# floppyemu.net
KiCad netlist of a schematic drawn in EAGLE
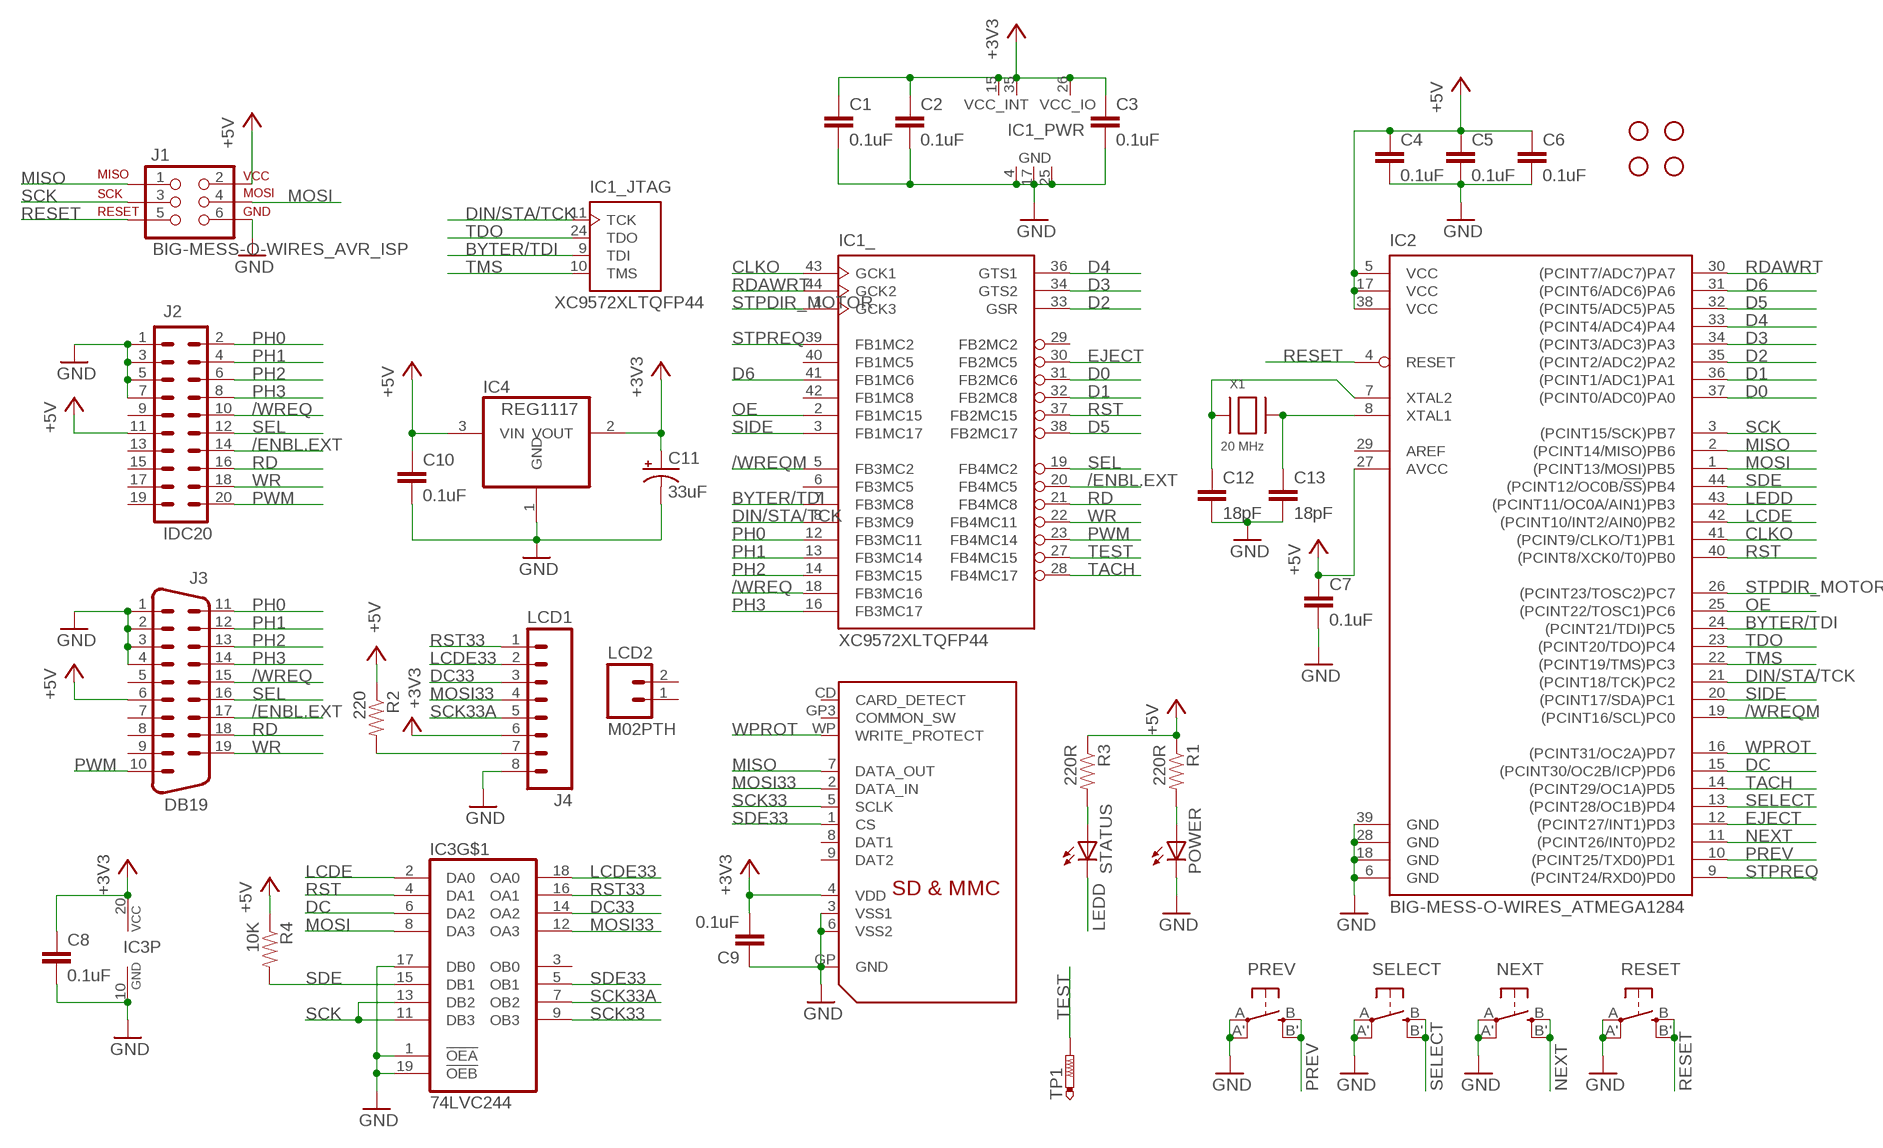
[diagram p0: schematic, sheet 1]

(export (version "E")
  (design (tool "Eeschema 10.0.6"))
  (components
    (comp (ref "C1")
      (value "0.1uF")
      (footprint "eagle-import:0805")
      (libsource (lib "eagle-import") (part "CAP0805"))
    )
    (comp (ref "C2")
      (value "0.1uF")
      (footprint "eagle-import:0805")
      (libsource (lib "eagle-import") (part "CAP0805"))
    )
    (comp (ref "C3")
      (value "0.1uF")
      (footprint "eagle-import:0805")
      (libsource (lib "eagle-import") (part "CAP0805"))
    )
    (comp (ref "C4")
      (value "0.1uF")
      (footprint "eagle-import:0805")
      (libsource (lib "eagle-import") (part "CAP0805"))
    )
    (comp (ref "C5")
      (value "0.1uF")
      (footprint "eagle-import:0805")
      (libsource (lib "eagle-import") (part "CAP0805"))
    )
    (comp (ref "C6")
      (value "0.1uF")
      (footprint "eagle-import:0805")
      (libsource (lib "eagle-import") (part "CAP0805"))
    )
    (comp (ref "C7")
      (value "0.1uF")
      (footprint "eagle-import:0805")
      (libsource (lib "eagle-import") (part "CAP0805"))
    )
    (comp (ref "C8")
      (value "0.1uF")
      (footprint "eagle-import:0805")
      (libsource (lib "eagle-import") (part "CAP0805"))
    )
    (comp (ref "C9")
      (value "0.1uF")
      (footprint "eagle-import:0805")
      (libsource (lib "eagle-import") (part "CAP0805"))
    )
    (comp (ref "C10")
      (value "0.1uF")
      (footprint "eagle-import:0805")
      (libsource (lib "eagle-import") (part "CAP0805"))
    )
    (comp (ref "C11")
      (value "33uF")
      (footprint "eagle-import:EIA3528")
      (libsource (lib "eagle-import") (part "47UF-TANT"))
    )
    (comp (ref "C12")
      (value "18pF")
      (footprint "eagle-import:0805")
      (libsource (lib "eagle-import") (part "CAP0805"))
    )
    (comp (ref "C13")
      (value "18pF")
      (footprint "eagle-import:0805")
      (libsource (lib "eagle-import") (part "CAP0805"))
    )
    (comp (ref "IC1")
      (value "XC9572XLTQFP44")
      (footprint "eagle-import:TQFP44-LONGPADS")
      (libsource (lib "eagle-import") (part "XC9572XLTQFP44"))
    )
    (comp (ref "IC2")
      (value "BIG-MESS-O-WIRES_ATMEGA1284")
      (footprint "eagle-import:BIG-MESS-O-WIRES_TQFP44-LONGPADS")
      (libsource (lib "eagle-import") (part "BIG-MESS-O-WIRES_ATMEGA1284"))
    )
    (comp (ref "IC3")
      (value "74LVC244")
      (footprint "eagle-import:SSOP20")
      (libsource (lib "eagle-import") (part "74X244"))
    )
    (comp (ref "IC4")
      (value "REG1117")
      (footprint "eagle-import:SOT223")
      (libsource (lib "eagle-import") (part "REG1117"))
    )
    (comp (ref "J1")
      (value "BIG-MESS-O-WIRES_AVR_ISP")
      (footprint "eagle-import:BIG-MESS-O-WIRES_2X3-SHROUDED")
      (libsource (lib "eagle-import") (part "BIG-MESS-O-WIRES_AVR_ISP"))
    )
    (comp (ref "J2")
      (value "IDC20")
      (footprint "eagle-import:IDC20")
      (libsource (lib "eagle-import") (part "IDC20"))
    )
    (comp (ref "J3")
      (value "DB19")
      (footprint "eagle-import:DB19EDGE")
      (libsource (lib "eagle-import") (part "DB19EDGE"))
    )
    (comp (ref "J4")
      (value "LCD1")
      (footprint "eagle-import:1X08")
      (libsource (lib "eagle-import") (part "M081X08"))
    )
    (comp (ref "LCD2")
      (value "M02PTH")
      (footprint "eagle-import:1X02")
      (libsource (lib "eagle-import") (part "M02PTH"))
    )
    (comp (ref "NEXT")
      (value "B3FS-10XX")
      (footprint "eagle-import:B3FS")
      (libsource (lib "eagle-import") (part "B3FS-10XX"))
    )
    (comp (ref "POWER")
      (value "LEDCHIPLED_0805")
      (footprint "eagle-import:CHIPLED_0805")
      (libsource (lib "eagle-import") (part "LEDCHIPLED_0805"))
    )
    (comp (ref "PREV")
      (value "B3FS-10XX")
      (footprint "eagle-import:B3FS")
      (libsource (lib "eagle-import") (part "B3FS-10XX"))
    )
    (comp (ref "R1")
      (value "220R")
      (footprint "eagle-import:0805")
      (libsource (lib "eagle-import") (part "RESISTOR0805-RES"))
    )
    (comp (ref "R2")
      (value "220")
      (footprint "eagle-import:1_6W-RES")
      (libsource (lib "eagle-import") (part "SparkFun-Resistors_RESISTORPTH-1/6W"))
    )
    (comp (ref "R3")
      (value "220R")
      (footprint "eagle-import:0805")
      (libsource (lib "eagle-import") (part "RESISTOR0805-RES"))
    )
    (comp (ref "R4")
      (value "10K")
      (footprint "eagle-import:0805")
      (libsource (lib "eagle-import") (part "RESISTOR0805-RES"))
    )
    (comp (ref "RESET")
      (value "B3FS-10XX")
      (footprint "eagle-import:B3FS")
      (libsource (lib "eagle-import") (part "B3FS-10XX"))
    )
    (comp (ref "SELECT")
      (value "B3FS-10XX")
      (footprint "eagle-import:B3FS")
      (libsource (lib "eagle-import") (part "B3FS-10XX"))
    )
    (comp (ref "STANDOFF1")
      (value "STAND-OFF")
      (footprint "eagle-import:STAND-OFF")
      (libsource (lib "eagle-import") (part "STAND-OFF"))
    )
    (comp (ref "STANDOFF2")
      (value "STAND-OFF")
      (footprint "eagle-import:STAND-OFF")
      (libsource (lib "eagle-import") (part "STAND-OFF"))
    )
    (comp (ref "STANDOFF3")
      (value "STAND-OFF")
      (footprint "eagle-import:STAND-OFF")
      (libsource (lib "eagle-import") (part "STAND-OFF"))
    )
    (comp (ref "STANDOFF4")
      (value "STAND-OFF")
      (footprint "eagle-import:STAND-OFF")
      (libsource (lib "eagle-import") (part "STAND-OFF"))
    )
    (comp (ref "STATUS")
      (value "LEDCHIPLED_0805")
      (footprint "eagle-import:CHIPLED_0805")
      (libsource (lib "eagle-import") (part "LEDCHIPLED_0805"))
    )
    (comp (ref "TP1")
      (value "PTR1PAD1-13")
      (footprint "eagle-import:P1-13")
      (libsource (lib "eagle-import") (part "PTR1PAD1-13"))
    )
    (comp (ref "U1")
      (value "ADAFRUIT_SDMMC06132")
      (footprint "eagle-import:ADAFRUIT_06132")
      (libsource (lib "eagle-import") (part "ADAFRUIT_SDMMC06132"))
    )
    (comp (ref "X1")
      (value "20 MHz")
      (footprint "eagle-import:NX5032")
      (libsource (lib "eagle-import") (part "XTALNX5032"))
    )
  )
  (nets
    (net (code "1") (name "+3V3") (class "Default")
      (node (ref "C1") (pin "1") (pinfunction "1_1") (pintype "passive"))
      (node (ref "C11") (pin "A") (pinfunction "+_A") (pintype "passive"))
      (node (ref "C2") (pin "1") (pinfunction "1_1") (pintype "passive"))
      (node (ref "C3") (pin "1") (pinfunction "1_1") (pintype "passive"))
      (node (ref "C8") (pin "1") (pinfunction "1_1") (pintype "passive"))
      (node (ref "C9") (pin "2") (pinfunction "2_2") (pintype "passive"))
      (node (ref "IC1") (pin "15") (pinfunction "VCC_INT_15") (pintype "power_in"))
      (node (ref "IC1") (pin "26") (pinfunction "VCC_IO_26") (pintype "power_in"))
      (node (ref "IC1") (pin "35") (pinfunction "VCC_INT_35") (pintype "power_in"))
      (node (ref "IC3") (pin "20") (pinfunction "VCC_20") (pintype "power_in"))
      (node (ref "IC4") (pin "2") (pinfunction "VOUT_2") (pintype "output"))
      (node (ref "J4") (pin "6") (pinfunction "6_6") (pintype "passive"))
      (node (ref "U1") (pin "4") (pinfunction "VDD_4") (pintype "power_in"))
    )
    (net (code "2") (name "+5V") (class "Default")
      (node (ref "C10") (pin "1") (pinfunction "1_1") (pintype "passive"))
      (node (ref "C4") (pin "1") (pinfunction "1_1") (pintype "passive"))
      (node (ref "C5") (pin "1") (pinfunction "1_1") (pintype "passive"))
      (node (ref "C6") (pin "1") (pinfunction "1_1") (pintype "passive"))
      (node (ref "C7") (pin "1") (pinfunction "1_1") (pintype "passive"))
      (node (ref "IC2") (pin "17") (pinfunction "VCC_17") (pintype "power_in"))
      (node (ref "IC2") (pin "27") (pinfunction "AVCC_27") (pintype "power_in"))
      (node (ref "IC2") (pin "38") (pinfunction "VCC_38") (pintype "power_in"))
      (node (ref "IC2") (pin "5") (pinfunction "VCC_5") (pintype "power_in"))
      (node (ref "IC4") (pin "3") (pinfunction "VIN_3") (pintype "input"))
      (node (ref "J1") (pin "2") (pinfunction "2_2") (pintype "passive"))
      (node (ref "J2") (pin "11") (pinfunction "11_11") (pintype "passive"))
      (node (ref "J3") (pin "6") (pinfunction "6_6") (pintype "passive"))
      (node (ref "R1") (pin "1") (pinfunction "1_1") (pintype "passive"))
      (node (ref "R2") (pin "1") (pinfunction "1_1") (pintype "passive"))
      (node (ref "R3") (pin "1") (pinfunction "1_1") (pintype "passive"))
      (node (ref "R4") (pin "1") (pinfunction "1_1") (pintype "passive"))
    )
    (net (code "3") (name "/BYTER{slash}TDI") (class "Default")
      (node (ref "IC1") (pin "7") (pinfunction "FB3MC8_7") (pintype "bidirectional"))
      (node (ref "IC1") (pin "9") (pinfunction "TDI_9") (pintype "input"))
      (node (ref "IC2") (pin "24") (pinfunction "(PCINT21/TDI)PC5_24") (pintype "output"))
    )
    (net (code "4") (name "/CLKO") (class "Default")
      (node (ref "IC1") (pin "43") (pinfunction "GCK1_43") (pintype "input"))
      (node (ref "IC2") (pin "41") (pinfunction "(PCINT9/CLKO/T1)PB1_41") (pintype "bidirectional"))
    )
    (net (code "5") (name "/D0") (class "Default")
      (node (ref "IC1") (pin "31") (pinfunction "FB2MC6_31") (pintype "bidirectional"))
      (node (ref "IC2") (pin "37") (pinfunction "(PCINT0/ADC0)PA0_37") (pintype "bidirectional"))
    )
    (net (code "6") (name "/D1") (class "Default")
      (node (ref "IC1") (pin "32") (pinfunction "FB2MC8_32") (pintype "bidirectional"))
      (node (ref "IC2") (pin "36") (pinfunction "(PCINT1/ADC1)PA1_36") (pintype "bidirectional"))
    )
    (net (code "7") (name "/D2") (class "Default")
      (node (ref "IC1") (pin "33") (pinfunction "GSR_33") (pintype "input"))
      (node (ref "IC2") (pin "35") (pinfunction "(PCINT2/ADC2)PA2_35") (pintype "bidirectional"))
    )
    (net (code "8") (name "/D3") (class "Default")
      (node (ref "IC1") (pin "34") (pinfunction "GTS2_34") (pintype "input"))
      (node (ref "IC2") (pin "34") (pinfunction "(PCINT3/ADC3)PA3_34") (pintype "bidirectional"))
    )
    (net (code "9") (name "/D4") (class "Default")
      (node (ref "IC1") (pin "36") (pinfunction "GTS1_36") (pintype "input"))
      (node (ref "IC2") (pin "33") (pinfunction "(PCINT4/ADC4)PA4_33") (pintype "bidirectional"))
    )
    (net (code "10") (name "/D5") (class "Default")
      (node (ref "IC1") (pin "38") (pinfunction "FB2MC17_38") (pintype "bidirectional"))
      (node (ref "IC2") (pin "32") (pinfunction "(PCINT5/ADC5)PA5_32") (pintype "bidirectional"))
    )
    (net (code "11") (name "/D6") (class "Default")
      (node (ref "IC1") (pin "41") (pinfunction "FB1MC6_41") (pintype "bidirectional"))
      (node (ref "IC2") (pin "31") (pinfunction "(PCINT6/ADC6)PA6_31") (pintype "bidirectional"))
    )
    (net (code "12") (name "/DC") (class "Default")
      (node (ref "IC2") (pin "15") (pinfunction "(PCINT30/OC2B/ICP)PD6_15") (pintype "bidirectional"))
      (node (ref "IC3") (pin "6") (pinfunction "DA2_6") (pintype "input"))
    )
    (net (code "13") (name "/DC33") (class "Default")
      (node (ref "IC3") (pin "14") (pinfunction "OA2_14") (pintype "output"))
      (node (ref "J4") (pin "3") (pinfunction "3_3") (pintype "passive"))
    )
    (net (code "14") (name "/DIN{slash}STA{slash}TCK") (class "Default")
      (node (ref "IC1") (pin "11") (pinfunction "TCK_11") (pintype "input"))
      (node (ref "IC1") (pin "8") (pinfunction "FB3MC9_8") (pintype "bidirectional"))
      (node (ref "IC2") (pin "21") (pinfunction "(PCINT18/TCK)PC2_21") (pintype "output"))
    )
    (net (code "15") (name "/EJECT") (class "Default")
      (node (ref "IC1") (pin "30") (pinfunction "FB2MC5_30") (pintype "bidirectional"))
      (node (ref "IC2") (pin "12") (pinfunction "(PCINT27/INT1)PD3_12") (pintype "bidirectional"))
    )
    (net (code "16") (name "/LCDE") (class "Default")
      (node (ref "IC2") (pin "42") (pinfunction "(PCINT10/INT2/AIN0)PB2_42") (pintype "bidirectional"))
      (node (ref "IC3") (pin "2") (pinfunction "DA0_2") (pintype "input"))
    )
    (net (code "17") (name "/LCDE33") (class "Default")
      (node (ref "IC3") (pin "18") (pinfunction "OA0_18") (pintype "output"))
      (node (ref "J4") (pin "2") (pinfunction "2_2") (pintype "passive"))
    )
    (net (code "18") (name "/LEDD") (class "Default")
      (node (ref "IC2") (pin "43") (pinfunction "(PCINT11/OC0A/AIN1)PB3_43") (pintype "bidirectional"))
      (node (ref "STATUS") (pin "C") (pinfunction "C_C") (pintype "passive"))
    )
    (net (code "19") (name "/MISO") (class "Default")
      (node (ref "IC2") (pin "2") (pinfunction "(PCINT14/MISO)PB6_2") (pintype "bidirectional"))
      (node (ref "J1") (pin "1") (pinfunction "1_1") (pintype "passive"))
      (node (ref "U1") (pin "7") (pinfunction "DATA_OUT_7") (pintype "output"))
    )
    (net (code "20") (name "/MOSI") (class "Default")
      (node (ref "IC2") (pin "1") (pinfunction "(PCINT13/MOSI)PB5_1") (pintype "bidirectional"))
      (node (ref "IC3") (pin "8") (pinfunction "DA3_8") (pintype "input"))
      (node (ref "J1") (pin "4") (pinfunction "4_4") (pintype "passive"))
    )
    (net (code "21") (name "/MOSI33") (class "Default")
      (node (ref "IC3") (pin "12") (pinfunction "OA3_12") (pintype "output"))
      (node (ref "J4") (pin "4") (pinfunction "4_4") (pintype "passive"))
      (node (ref "U1") (pin "2") (pinfunction "DATA_IN_2") (pintype "input"))
    )
    (net (code "22") (name "/NEXT") (class "Default")
      (node (ref "IC2") (pin "11") (pinfunction "(PCINT26/INT0)PD2_11") (pintype "bidirectional"))
      (node (ref "NEXT") (pin "B") (pinfunction "B_B") (pintype "passive"))
      (node (ref "NEXT") (pin "B'") (pinfunction "B'_B'") (pintype "passive"))
    )
    (net (code "23") (name "/OE") (class "Default")
      (node (ref "IC1") (pin "2") (pinfunction "FB1MC15_2") (pintype "bidirectional"))
      (node (ref "IC2") (pin "25") (pinfunction "(PCINT22/TOSC1)PC6_25") (pintype "output"))
    )
    (net (code "24") (name "/PH0") (class "Default")
      (node (ref "IC1") (pin "12") (pinfunction "FB3MC11_12") (pintype "bidirectional"))
      (node (ref "J2") (pin "2") (pinfunction "2_2") (pintype "passive"))
      (node (ref "J3") (pin "11") (pinfunction "11_11") (pintype "passive"))
    )
    (net (code "25") (name "/PH1") (class "Default")
      (node (ref "IC1") (pin "13") (pinfunction "FB3MC14_13") (pintype "bidirectional"))
      (node (ref "J2") (pin "4") (pinfunction "4_4") (pintype "passive"))
      (node (ref "J3") (pin "12") (pinfunction "12_12") (pintype "passive"))
    )
    (net (code "26") (name "/PH2") (class "Default")
      (node (ref "IC1") (pin "14") (pinfunction "FB3MC15_14") (pintype "bidirectional"))
      (node (ref "J2") (pin "6") (pinfunction "6_6") (pintype "passive"))
      (node (ref "J3") (pin "13") (pinfunction "13_13") (pintype "passive"))
    )
    (net (code "27") (name "/PH3") (class "Default")
      (node (ref "IC1") (pin "16") (pinfunction "FB3MC17_16") (pintype "bidirectional"))
      (node (ref "J2") (pin "8") (pinfunction "8_8") (pintype "passive"))
      (node (ref "J3") (pin "14") (pinfunction "14_14") (pintype "passive"))
    )
    (net (code "28") (name "/PREV") (class "Default")
      (node (ref "IC2") (pin "10") (pinfunction "(PCINT25/TXD0)PD1_10") (pintype "bidirectional"))
      (node (ref "PREV") (pin "B") (pinfunction "B_B") (pintype "passive"))
      (node (ref "PREV") (pin "B'") (pinfunction "B'_B'") (pintype "passive"))
    )
    (net (code "29") (name "/PWM") (class "Default")
      (node (ref "IC1") (pin "23") (pinfunction "FB4MC14_23") (pintype "bidirectional"))
      (node (ref "J2") (pin "20") (pinfunction "20_20") (pintype "passive"))
      (node (ref "J3") (pin "10") (pinfunction "10_10") (pintype "passive"))
    )
    (net (code "30") (name "/RD") (class "Default")
      (node (ref "IC1") (pin "21") (pinfunction "FB4MC8_21") (pintype "bidirectional"))
      (node (ref "J2") (pin "16") (pinfunction "16_16") (pintype "passive"))
      (node (ref "J3") (pin "18") (pinfunction "18_18") (pintype "passive"))
    )
    (net (code "31") (name "/RDAWRT") (class "Default")
      (node (ref "IC1") (pin "44") (pinfunction "GCK2_44") (pintype "input"))
      (node (ref "IC2") (pin "30") (pinfunction "(PCINT7/ADC7)PA7_30") (pintype "bidirectional"))
    )
    (net (code "32") (name "/RESET") (class "Default")
      (node (ref "IC2") (pin "4") (pinfunction "RESET_4") (pintype "input"))
      (node (ref "J1") (pin "5") (pinfunction "5_5") (pintype "passive"))
      (node (ref "RESET") (pin "B") (pinfunction "B_B") (pintype "passive"))
      (node (ref "RESET") (pin "B'") (pinfunction "B'_B'") (pintype "passive"))
    )
    (net (code "33") (name "/RST") (class "Default")
      (node (ref "IC1") (pin "37") (pinfunction "FB2MC15_37") (pintype "bidirectional"))
      (node (ref "IC2") (pin "40") (pinfunction "(PCINT8/XCK0/T0)PB0_40") (pintype "bidirectional"))
      (node (ref "IC3") (pin "4") (pinfunction "DA1_4") (pintype "input"))
    )
    (net (code "34") (name "/RST33") (class "Default")
      (node (ref "IC3") (pin "16") (pinfunction "OA1_16") (pintype "output"))
      (node (ref "J4") (pin "1") (pinfunction "1_1") (pintype "passive"))
    )
    (net (code "35") (name "/SCK") (class "Default")
      (node (ref "IC2") (pin "3") (pinfunction "(PCINT15/SCK)PB7_3") (pintype "bidirectional"))
      (node (ref "IC3") (pin "11") (pinfunction "DB3_11") (pintype "input"))
      (node (ref "IC3") (pin "13") (pinfunction "DB2_13") (pintype "input"))
      (node (ref "J1") (pin "3") (pinfunction "3_3") (pintype "passive"))
    )
    (net (code "36") (name "/SCK33") (class "Default")
      (node (ref "IC3") (pin "9") (pinfunction "OB3_9") (pintype "output"))
      (node (ref "U1") (pin "5") (pinfunction "SCLK_5") (pintype "input"))
    )
    (net (code "37") (name "/SCK33A") (class "Default")
      (node (ref "IC3") (pin "7") (pinfunction "OB2_7") (pintype "output"))
      (node (ref "J4") (pin "5") (pinfunction "5_5") (pintype "passive"))
    )
    (net (code "38") (name "/SDE") (class "Default")
      (node (ref "IC2") (pin "44") (pinfunction "(PCINT12/OC0B/~{SS})PB4_44") (pintype "bidirectional"))
      (node (ref "IC3") (pin "15") (pinfunction "DB1_15") (pintype "input"))
      (node (ref "R4") (pin "2") (pinfunction "2_2") (pintype "passive"))
    )
    (net (code "39") (name "/SDE33") (class "Default")
      (node (ref "IC3") (pin "5") (pinfunction "OB1_5") (pintype "output"))
      (node (ref "U1") (pin "1") (pinfunction "CS_1") (pintype "input"))
    )
    (net (code "40") (name "/SEL") (class "Default")
      (node (ref "IC1") (pin "19") (pinfunction "FB4MC2_19") (pintype "bidirectional"))
      (node (ref "J2") (pin "12") (pinfunction "12_12") (pintype "passive"))
      (node (ref "J3") (pin "16") (pinfunction "16_16") (pintype "passive"))
    )
    (net (code "41") (name "/SELECT") (class "Default")
      (node (ref "IC2") (pin "13") (pinfunction "(PCINT28/OC1B)PD4_13") (pintype "bidirectional"))
      (node (ref "SELECT") (pin "B") (pinfunction "B_B") (pintype "passive"))
      (node (ref "SELECT") (pin "B'") (pinfunction "B'_B'") (pintype "passive"))
    )
    (net (code "42") (name "/SIDE") (class "Default")
      (node (ref "IC1") (pin "3") (pinfunction "FB1MC17_3") (pintype "bidirectional"))
      (node (ref "IC2") (pin "20") (pinfunction "(PCINT17/SDA)PC1_20") (pintype "output"))
    )
    (net (code "43") (name "/STPDIR_MOTOR") (class "Default")
      (node (ref "IC1") (pin "1") (pinfunction "GCK3_1") (pintype "input"))
      (node (ref "IC2") (pin "26") (pinfunction "(PCINT23/TOSC2)PC7_26") (pintype "output"))
    )
    (net (code "44") (name "/STPREQ") (class "Default")
      (node (ref "IC1") (pin "39") (pinfunction "FB1MC2_39") (pintype "bidirectional"))
      (node (ref "IC2") (pin "9") (pinfunction "(PCINT24/RXD0)PD0_9") (pintype "bidirectional"))
    )
    (net (code "45") (name "/TACH") (class "Default")
      (node (ref "IC1") (pin "28") (pinfunction "FB4MC17_28") (pintype "bidirectional"))
      (node (ref "IC2") (pin "14") (pinfunction "(PCINT29/OC1A)PD5_14") (pintype "bidirectional"))
    )
    (net (code "46") (name "/TDO") (class "Default")
      (node (ref "IC1") (pin "24") (pinfunction "TDO_24") (pintype "output"))
      (node (ref "IC2") (pin "23") (pinfunction "(PCINT20/TDO)PC4_23") (pintype "output"))
    )
    (net (code "47") (name "/TEST") (class "Default")
      (node (ref "IC1") (pin "27") (pinfunction "FB4MC15_27") (pintype "bidirectional"))
      (node (ref "TP1") (pin "TP") (pinfunction "TP_TP") (pintype "input"))
    )
    (net (code "48") (name "/TMS") (class "Default")
      (node (ref "IC1") (pin "10") (pinfunction "TMS_10") (pintype "input"))
      (node (ref "IC2") (pin "22") (pinfunction "(PCINT19/TMS)PC3_22") (pintype "output"))
    )
    (net (code "49") (name "/WPROT") (class "Default")
      (node (ref "IC2") (pin "16") (pinfunction "(PCINT31/OC2A)PD7_16") (pintype "bidirectional"))
      (node (ref "U1") (pin "WP") (pinfunction "WRITE_PROTECT_WP") (pintype "passive"))
    )
    (net (code "50") (name "/WR") (class "Default")
      (node (ref "IC1") (pin "22") (pinfunction "FB4MC11_22") (pintype "bidirectional"))
      (node (ref "J2") (pin "18") (pinfunction "18_18") (pintype "passive"))
      (node (ref "J3") (pin "19") (pinfunction "19_19") (pintype "passive"))
    )
    (net (code "51") (name "/{slash}ENBL.EXT") (class "Default")
      (node (ref "IC1") (pin "20") (pinfunction "FB4MC5_20") (pintype "bidirectional"))
      (node (ref "J2") (pin "14") (pinfunction "14_14") (pintype "passive"))
      (node (ref "J3") (pin "17") (pinfunction "17_17") (pintype "passive"))
    )
    (net (code "52") (name "/{slash}WREQ") (class "Default")
      (node (ref "IC1") (pin "18") (pinfunction "FB3MC16_18") (pintype "bidirectional"))
      (node (ref "J2") (pin "10") (pinfunction "10_10") (pintype "passive"))
      (node (ref "J3") (pin "15") (pinfunction "15_15") (pintype "passive"))
    )
    (net (code "53") (name "/{slash}WREQM") (class "Default")
      (node (ref "IC1") (pin "5") (pinfunction "FB3MC2_5") (pintype "bidirectional"))
      (node (ref "IC2") (pin "19") (pinfunction "(PCINT16/SCL)PC0_19") (pintype "output"))
    )
    (net (code "54") (name "GND") (class "Default")
      (node (ref "C1") (pin "2") (pinfunction "2_2") (pintype "passive"))
      (node (ref "C10") (pin "2") (pinfunction "2_2") (pintype "passive"))
      (node (ref "C11") (pin "C") (pinfunction "-_C") (pintype "passive"))
      (node (ref "C12") (pin "2") (pinfunction "2_2") (pintype "passive"))
      (node (ref "C13") (pin "2") (pinfunction "2_2") (pintype "passive"))
      (node (ref "C2") (pin "2") (pinfunction "2_2") (pintype "passive"))
      (node (ref "C3") (pin "2") (pinfunction "2_2") (pintype "passive"))
      (node (ref "C4") (pin "2") (pinfunction "2_2") (pintype "passive"))
      (node (ref "C5") (pin "2") (pinfunction "2_2") (pintype "passive"))
      (node (ref "C6") (pin "2") (pinfunction "2_2") (pintype "passive"))
      (node (ref "C7") (pin "2") (pinfunction "2_2") (pintype "passive"))
      (node (ref "C8") (pin "2") (pinfunction "2_2") (pintype "passive"))
      (node (ref "C9") (pin "1") (pinfunction "1_1") (pintype "passive"))
      (node (ref "IC1") (pin "17") (pinfunction "GND_17") (pintype "power_in"))
      (node (ref "IC1") (pin "25") (pinfunction "GND_25") (pintype "power_in"))
      (node (ref "IC1") (pin "4") (pinfunction "GND_4") (pintype "power_in"))
      (node (ref "IC2") (pin "18") (pinfunction "GND_18") (pintype "power_in"))
      (node (ref "IC2") (pin "28") (pinfunction "GND_28") (pintype "power_in"))
      (node (ref "IC2") (pin "39") (pinfunction "GND_39") (pintype "power_in"))
      (node (ref "IC2") (pin "6") (pinfunction "GND_6") (pintype "power_in"))
      (node (ref "IC3") (pin "1") (pinfunction "~{OEA}_1") (pintype "input"))
      (node (ref "IC3") (pin "10") (pinfunction "GND_10") (pintype "power_in"))
      (node (ref "IC3") (pin "17") (pinfunction "DB0_17") (pintype "input"))
      (node (ref "IC3") (pin "19") (pinfunction "~{OEB}_19") (pintype "input"))
      (node (ref "IC4") (pin "1") (pinfunction "GND_1") (pintype "power_in"))
      (node (ref "J1") (pin "6") (pinfunction "6_6") (pintype "passive"))
      (node (ref "J2") (pin "1") (pinfunction "1_1") (pintype "passive"))
      (node (ref "J2") (pin "3") (pinfunction "3_3") (pintype "passive"))
      (node (ref "J2") (pin "5") (pinfunction "5_5") (pintype "passive"))
      (node (ref "J2") (pin "7") (pinfunction "7_7") (pintype "passive"))
      (node (ref "J3") (pin "1") (pinfunction "1_1") (pintype "passive"))
      (node (ref "J3") (pin "2") (pinfunction "2_2") (pintype "passive"))
      (node (ref "J3") (pin "3") (pinfunction "3_3") (pintype "passive"))
      (node (ref "J3") (pin "4") (pinfunction "4_4") (pintype "passive"))
      (node (ref "J4") (pin "8") (pinfunction "8_8") (pintype "passive"))
      (node (ref "NEXT") (pin "A") (pinfunction "A_A") (pintype "passive"))
      (node (ref "NEXT") (pin "A'") (pinfunction "A'_A'") (pintype "passive"))
      (node (ref "POWER") (pin "C") (pinfunction "C_C") (pintype "passive"))
      (node (ref "PREV") (pin "A") (pinfunction "A_A") (pintype "passive"))
      (node (ref "PREV") (pin "A'") (pinfunction "A'_A'") (pintype "passive"))
      (node (ref "RESET") (pin "A") (pinfunction "A_A") (pintype "passive"))
      (node (ref "RESET") (pin "A'") (pinfunction "A'_A'") (pintype "passive"))
      (node (ref "SELECT") (pin "A") (pinfunction "A_A") (pintype "passive"))
      (node (ref "SELECT") (pin "A'") (pinfunction "A'_A'") (pintype "passive"))
      (node (ref "U1") (pin "3") (pinfunction "VSS1_3") (pintype "power_in"))
      (node (ref "U1") (pin "6") (pinfunction "VSS2_6") (pintype "power_in"))
      (node (ref "U1") (pin "GP") (pinfunction "GND_GP") (pintype "power_in"))
    )
    (net (code "55") (name "Net-(IC2-XTAL1)") (class "Default")
      (node (ref "C13") (pin "1") (pinfunction "1_1") (pintype "passive"))
      (node (ref "IC2") (pin "8") (pinfunction "XTAL1_8") (pintype "bidirectional"))
      (node (ref "X1") (pin "P$2") (pinfunction "P$2_P$2") (pintype "bidirectional"))
    )
    (net (code "56") (name "Net-(IC2-XTAL2)") (class "Default")
      (node (ref "C12") (pin "1") (pinfunction "1_1") (pintype "passive"))
      (node (ref "IC2") (pin "7") (pinfunction "XTAL2_7") (pintype "bidirectional"))
      (node (ref "X1") (pin "P$1") (pinfunction "P$1_P$1") (pintype "bidirectional"))
    )
    (net (code "57") (name "Net-(J4-Pad7)") (class "Default")
      (node (ref "J4") (pin "7") (pinfunction "7_7") (pintype "passive"))
      (node (ref "R2") (pin "2") (pinfunction "2_2") (pintype "passive"))
    )
    (net (code "58") (name "Net-(POWER-PadA)") (class "Default")
      (node (ref "POWER") (pin "A") (pinfunction "A_A") (pintype "passive"))
      (node (ref "R1") (pin "2") (pinfunction "2_2") (pintype "passive"))
    )
    (net (code "59") (name "Net-(R3-Pad2)") (class "Default")
      (node (ref "R3") (pin "2") (pinfunction "2_2") (pintype "passive"))
      (node (ref "STATUS") (pin "A") (pinfunction "A_A") (pintype "passive"))
    )
    (net (code "60") (name "unconnected-(IC1A-FB1MC5-Pad40)") (class "Default")
      (node (ref "IC1") (pin "40") (pinfunction "FB1MC5_40") (pintype "bidirectional"))
    )
    (net (code "61") (name "unconnected-(IC1A-FB1MC8-Pad42)") (class "Default")
      (node (ref "IC1") (pin "42") (pinfunction "FB1MC8_42") (pintype "bidirectional"))
    )
    (net (code "62") (name "unconnected-(IC1A-FB2MC2-Pad29)") (class "Default")
      (node (ref "IC1") (pin "29") (pinfunction "FB2MC2_29") (pintype "bidirectional"))
    )
    (net (code "63") (name "unconnected-(IC1A-FB3MC5-Pad6)") (class "Default")
      (node (ref "IC1") (pin "6") (pinfunction "FB3MC5_6") (pintype "bidirectional"))
    )
    (net (code "64") (name "unconnected-(IC2-AREF-Pad29)") (class "Default")
      (node (ref "IC2") (pin "29") (pinfunction "AREF_29") (pintype "passive"))
    )
    (net (code "65") (name "unconnected-(IC3A-OB0-Pad3)") (class "Default")
      (node (ref "IC3") (pin "3") (pinfunction "OB0_3") (pintype "output"))
    )
    (net (code "66") (name "unconnected-(J2-Pad9)") (class "Default")
      (node (ref "J2") (pin "9") (pinfunction "9_9") (pintype "passive"))
    )
    (net (code "67") (name "unconnected-(J2-Pad13)") (class "Default")
      (node (ref "J2") (pin "13") (pinfunction "13_13") (pintype "passive"))
    )
    (net (code "68") (name "unconnected-(J2-Pad15)") (class "Default")
      (node (ref "J2") (pin "15") (pinfunction "15_15") (pintype "passive"))
    )
    (net (code "69") (name "unconnected-(J2-Pad17)") (class "Default")
      (node (ref "J2") (pin "17") (pinfunction "17_17") (pintype "passive"))
    )
    (net (code "70") (name "unconnected-(J2-Pad19)") (class "Default")
      (node (ref "J2") (pin "19") (pinfunction "19_19") (pintype "passive"))
    )
    (net (code "71") (name "unconnected-(J3-Pad5)") (class "Default")
      (node (ref "J3") (pin "5") (pinfunction "5_5") (pintype "passive"))
    )
    (net (code "72") (name "unconnected-(J3-Pad7)") (class "Default")
      (node (ref "J3") (pin "7") (pinfunction "7_7") (pintype "passive"))
    )
    (net (code "73") (name "unconnected-(J3-Pad8)") (class "Default")
      (node (ref "J3") (pin "8") (pinfunction "8_8") (pintype "passive"))
    )
    (net (code "74") (name "unconnected-(J3-Pad9)") (class "Default")
      (node (ref "J3") (pin "9") (pinfunction "9_9") (pintype "passive"))
    )
    (net (code "75") (name "unconnected-(LCD2-Pad1)") (class "Default")
      (node (ref "LCD2") (pin "1") (pinfunction "1_1") (pintype "passive"))
    )
    (net (code "76") (name "unconnected-(LCD2-Pad2)") (class "Default")
      (node (ref "LCD2") (pin "2") (pinfunction "2_2") (pintype "passive"))
    )
    (net (code "77") (name "unconnected-(U1-CARD_DETECT-PadCD)") (class "Default")
      (node (ref "U1") (pin "CD") (pinfunction "CARD_DETECT_CD") (pintype "passive"))
    )
    (net (code "78") (name "unconnected-(U1-COMMON_SW-PadGP3)") (class "Default")
      (node (ref "U1") (pin "GP3") (pinfunction "COMMON_SW_GP3") (pintype "passive"))
    )
    (net (code "79") (name "unconnected-(U1-DAT1-Pad8)") (class "Default")
      (node (ref "U1") (pin "8") (pinfunction "DAT1_8") (pintype "bidirectional"))
    )
    (net (code "80") (name "unconnected-(U1-DAT2-Pad9)") (class "Default")
      (node (ref "U1") (pin "9") (pinfunction "DAT2_9") (pintype "bidirectional"))
    )
  )
)
